# Connectors.net
KiCad netlist of a schematic drawn in Altium Designer
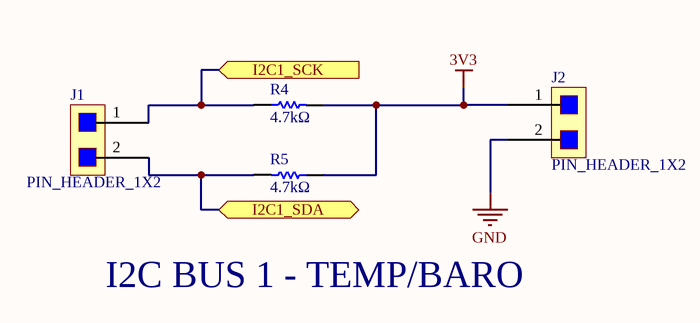
[diagram p0: Connectors.SchDoc]

(export (version "E")
  (design (tool "Eeschema 10.0.6"))
  (components
    (comp (ref "J1")
      (value "PIN_HEADER_1X2")
      (footprint "PIN_HEADER - 1X2")
      (description "Board Connector, 1 Contact(s), 1 Row(s), Male, Straight, Solder Terminal")
      (fields
        (field (name "MANUFACTURER") "Sullins")
        (field (name "MANUFACTURER PART NUMBER") "PREC001SAAN-RC")
      )
      (libsource (lib "SKALE_LIB") (part "PIN_HEADER_1X2"))
    )
    (comp (ref "J2")
      (value "PIN_HEADER_1X2")
      (footprint "PIN_HEADER - 1X2")
      (description "Board Connector, 1 Contact(s), 1 Row(s), Male, Straight, Solder Terminal")
      (fields
        (field (name "MANUFACTURER") "Sullins")
        (field (name "MANUFACTURER PART NUMBER") "PREC001SAAN-RC")
      )
      (libsource (lib "") (part "PIN_HEADER_1X2_1"))
    )
    (comp (ref "R4")
      (value "4.7kΩ")
      (footprint "RES0603")
      (description "RES 4.7K OHM 5% 1/10W 0603")
      (fields (field (name "Comment") "RES_4.7kΩ_0603"))
      (libsource (lib "SKALE_LIB") (part "RES_4.7kΩ_0603_5%"))
    )
    (comp (ref "R5")
      (value "4.7kΩ")
      (footprint "RES0603")
      (description "RES 4.7K OHM 5% 1/10W 0603")
      (fields (field (name "Comment") "RES_4.7kΩ_0603"))
      (libsource (lib "SKALE_LIB") (part "RES_4.7kΩ_0603_5%"))
    )
  )
  (nets
    (net (code "1") (name "/I2C1_SCK") (class "Default")
      (node (ref "J1") (pin "1") (pinfunction "0_1") (pintype "passive"))
      (node (ref "R4") (pin "1") (pinfunction "1_1") (pintype "passive"))
    )
    (net (code "2") (name "/I2C1_SDA") (class "Default")
      (node (ref "J1") (pin "2") (pinfunction "0_2") (pintype "passive"))
      (node (ref "R5") (pin "2") (pinfunction "2_2") (pintype "passive"))
    )
    (net (code "3") (name "3V3") (class "Default")
      (node (ref "J2") (pin "1") (pinfunction "0_1") (pintype "passive"))
      (node (ref "R4") (pin "2") (pinfunction "2_2") (pintype "passive"))
      (node (ref "R5") (pin "1") (pinfunction "1_1") (pintype "passive"))
    )
    (net (code "4") (name "GND") (class "Default")
      (node (ref "J2") (pin "2") (pinfunction "0_2") (pintype "passive"))
    )
  )
)
